# REF-Controller.net
KiCad netlist of a schematic drawn in Altium Designer
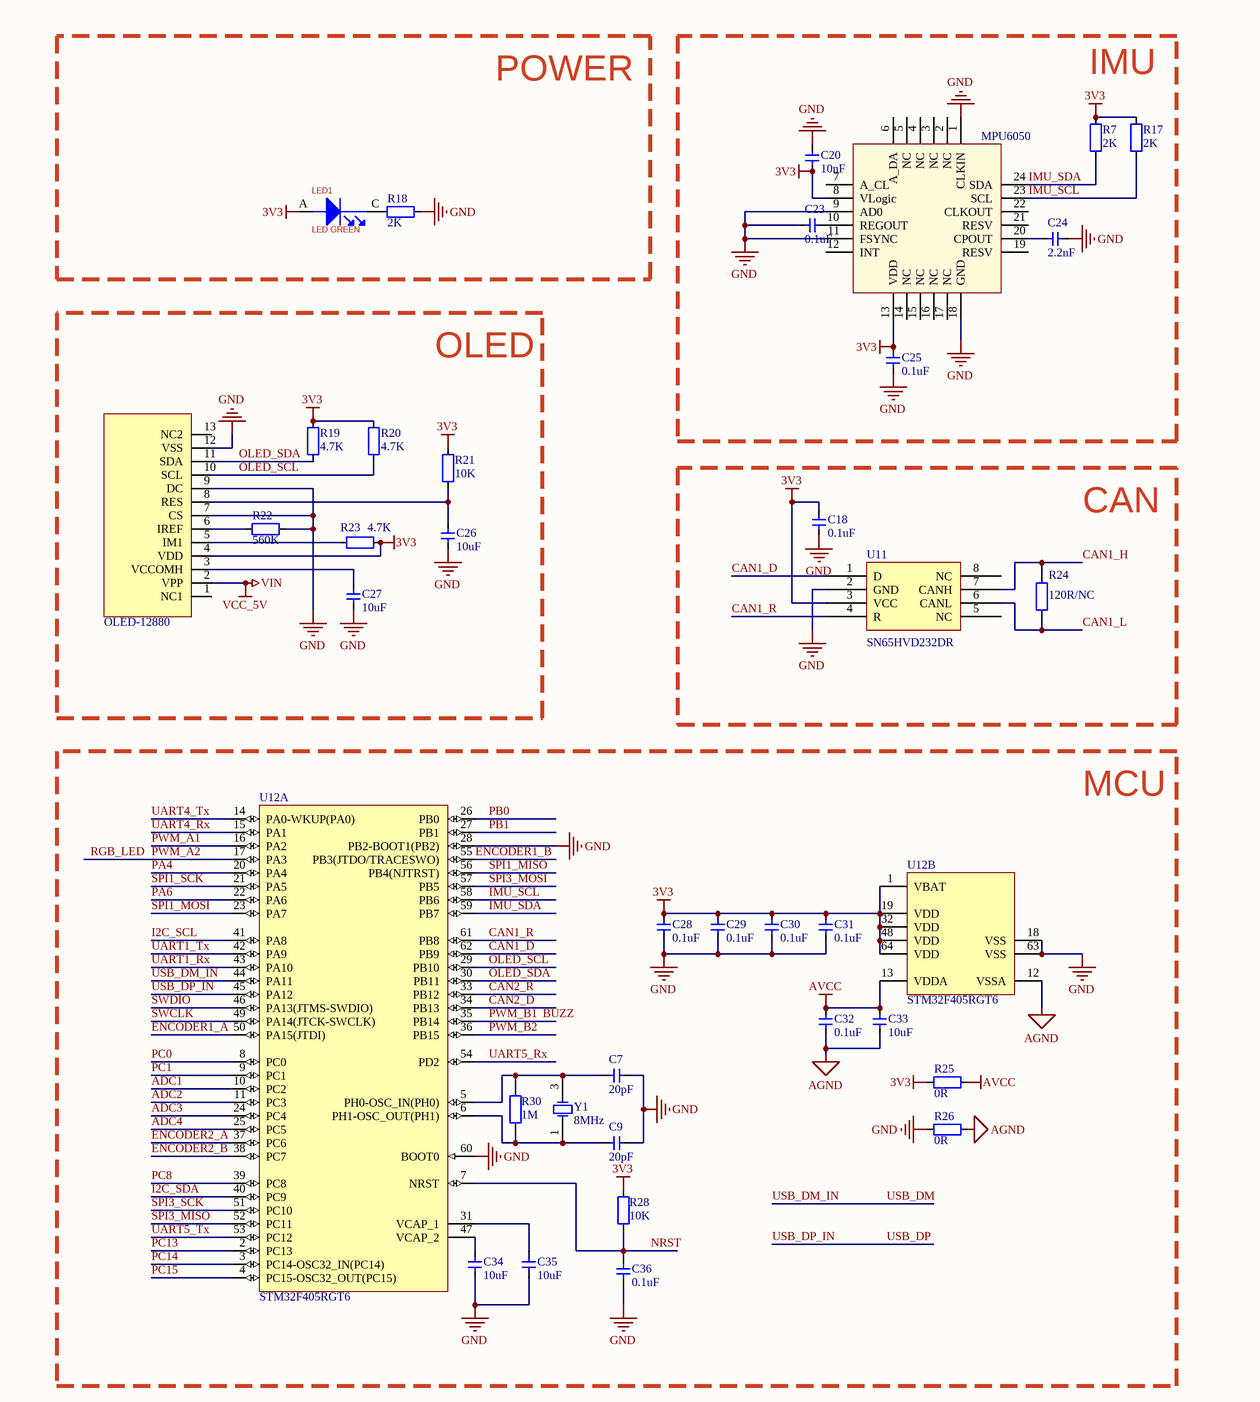
[diagram p0: REF-Controller.SchDoc, top]
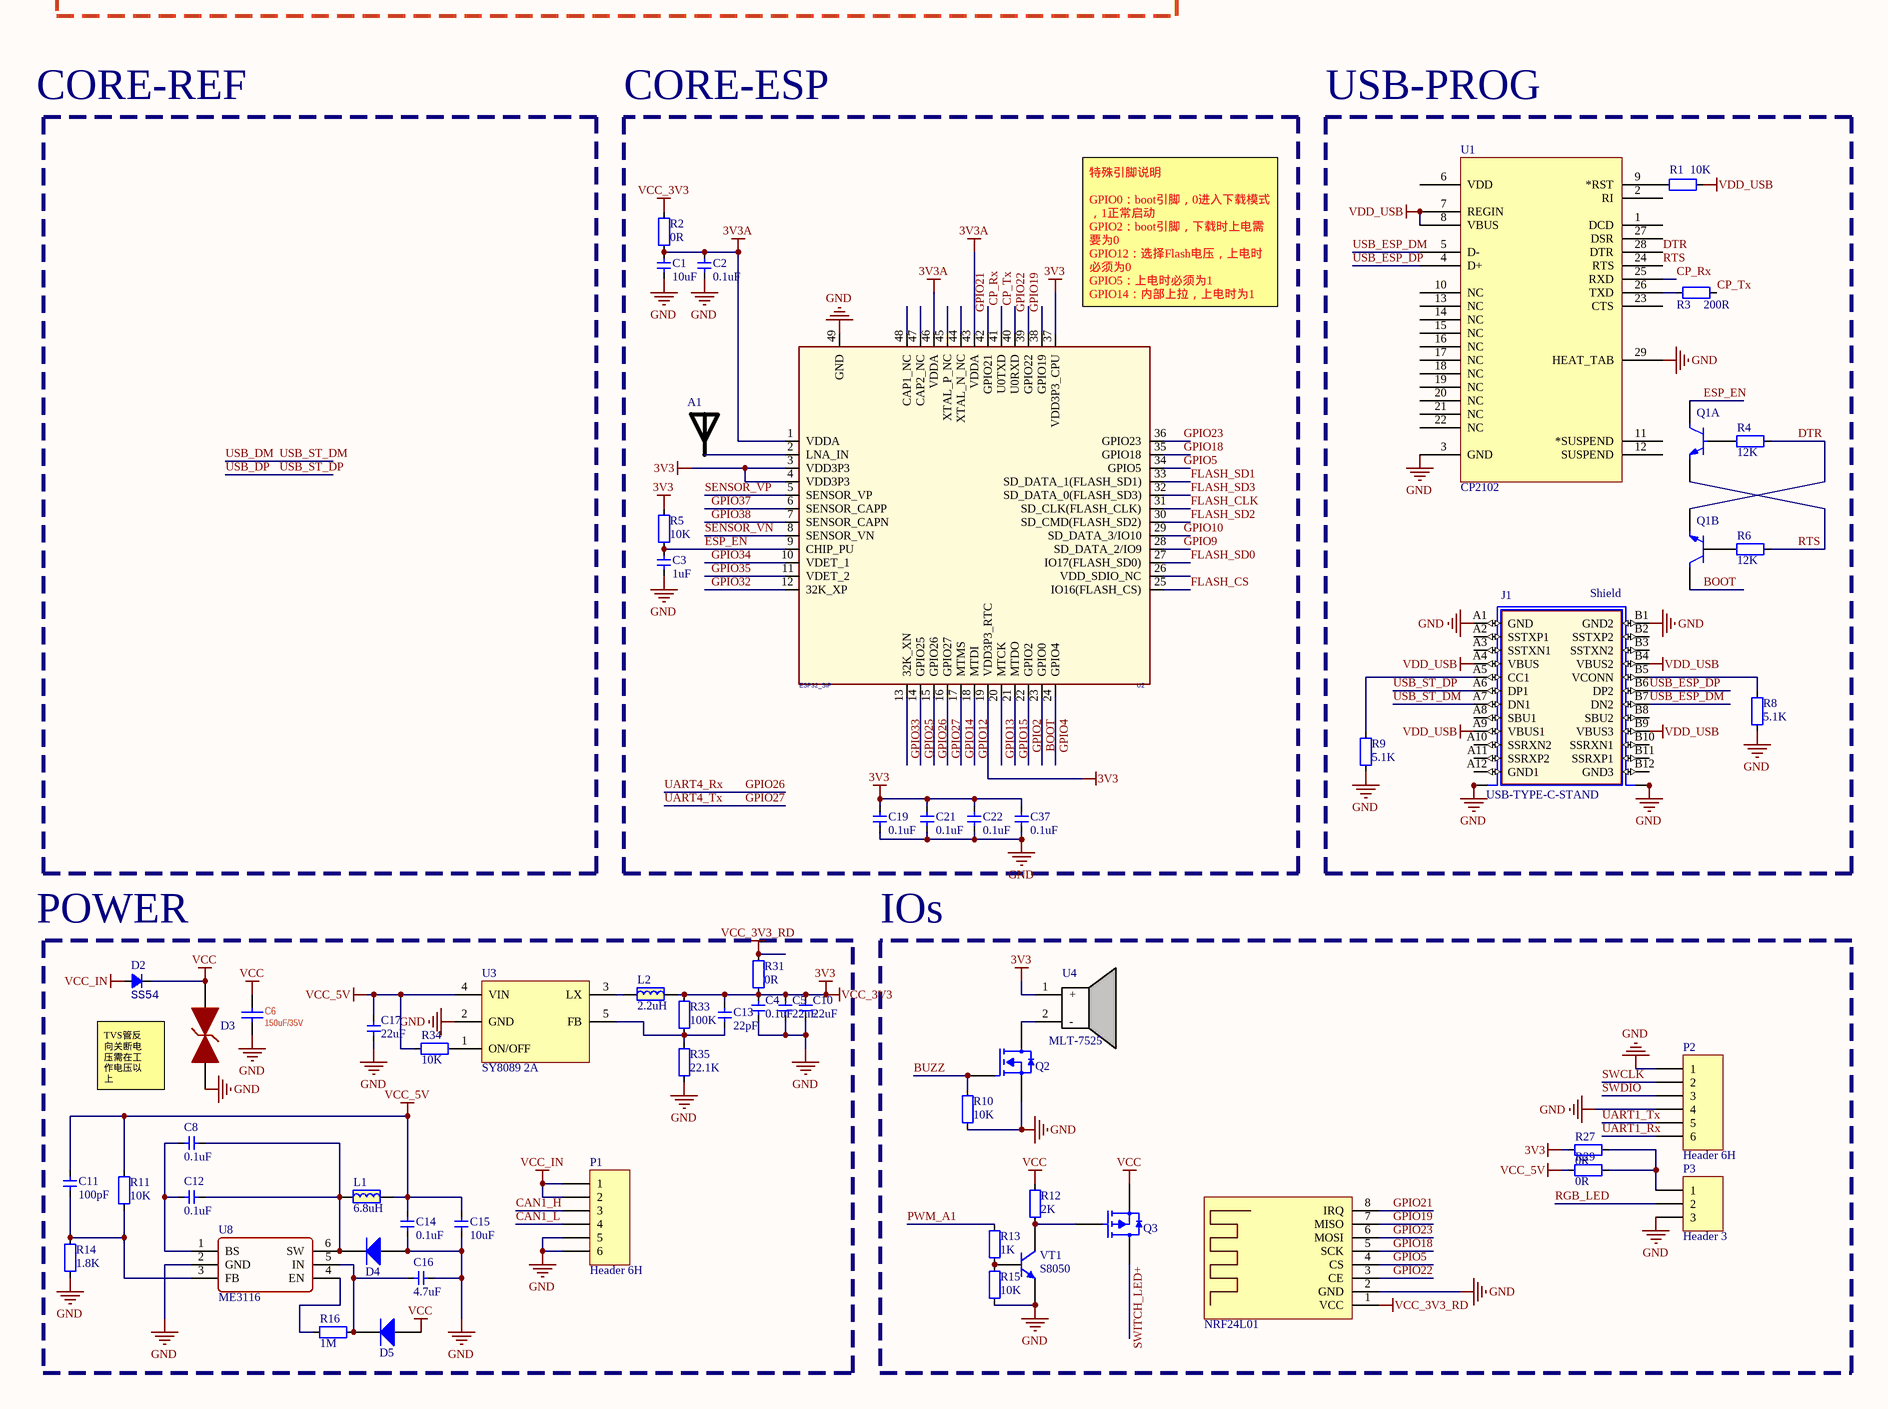
[diagram p1: REF-Controller.SchDoc, bottom]

(export (version "E")
  (design (tool "Eeschema 10.0.6"))
  (components
    (comp (ref "1")
      (value "OLED-12880")
      (footprint "OLED-12880")
      (libsource (lib "mLib") (part "OLED-12880"))
    )
    (comp (ref "A1")
      (value "RAINSUN")
      (footprint "ANT-Rainsun-AN5120")
      (libsource (lib "MyPcbLib") (part "ANT-Rainsun-AP5120"))
    )
    (comp (ref "C1")
      (value "10uF")
      (footprint "CAP_0402")
      (description "Capacitor")
      (libsource (lib "MyPcbLib") (part "电容-0402"))
    )
    (comp (ref "C2")
      (value "0.1uF")
      (footprint "CAP_0402")
      (description "Capacitor")
      (libsource (lib "MyPcbLib") (part "电容-0402"))
    )
    (comp (ref "C3")
      (value "1uF")
      (footprint "CAP_0402")
      (description "Capacitor")
      (libsource (lib "MyPcbLib") (part "电容-0402"))
    )
    (comp (ref "C4")
      (value "0.1uF")
      (footprint "CAP_0402")
      (description "Capacitor")
      (libsource (lib "MyPcbLib") (part "电容-0402"))
    )
    (comp (ref "C5")
      (value "22uF")
      (footprint "C0603")
      (description "Capacitor")
      (libsource (lib "MyPcbLib") (part "电容-0402"))
    )
    (comp (ref "C6")
      (value "150uF/35V")
      (footprint "CAP-SMD_BD8.0-L8.3-W8.3-LS9.3-FD")
      (description "Capacitor, chip, ceramic")
      (fields (field (name "Comment") "220uF/25V"))
      (libsource (lib "OAKUSBFXS") (part "CAP"))
    )
    (comp (ref "C7")
      (value "20pF")
      (footprint "CAP_0402")
      (description "Capacitor")
      (libsource (lib "MyPcbLib") (part "电容-0402"))
    )
    (comp (ref "C8")
      (value "0.1uF")
      (footprint "CAP_0402")
      (description "Capacitor")
      (libsource (lib "MyPcbLib") (part "电容-0402"))
    )
    (comp (ref "C9")
      (value "20pF")
      (footprint "CAP_0402")
      (description "Capacitor")
      (libsource (lib "MyPcbLib") (part "电容-0402"))
    )
    (comp (ref "C10")
      (value "22uF")
      (footprint "C0603")
      (description "Capacitor")
      (libsource (lib "MyPcbLib") (part "电容-0402"))
    )
    (comp (ref "C11")
      (value "100pF")
      (footprint "CAP_0402")
      (description "Capacitor")
      (libsource (lib "MyPcbLib") (part "电容-0402"))
    )
    (comp (ref "C12")
      (value "0.1uF")
      (footprint "CAP_0402")
      (description "Capacitor")
      (libsource (lib "MyPcbLib") (part "电容-0402"))
    )
    (comp (ref "C13")
      (value "22pF")
      (footprint "CAP_0402")
      (description "Capacitor")
      (libsource (lib "MyPcbLib") (part "电容-0402"))
    )
    (comp (ref "C14")
      (value "0.1uF")
      (footprint "CAP_0402")
      (description "Capacitor")
      (libsource (lib "MyPcbLib") (part "电容-0402"))
    )
    (comp (ref "C15")
      (value "10uF")
      (footprint "CAP_0402")
      (description "Capacitor")
      (libsource (lib "MyPcbLib") (part "电容-0402"))
    )
    (comp (ref "C16")
      (value "4.7uF")
      (footprint "C0603")
      (description "Capacitor")
      (libsource (lib "MyPcbLib") (part "电容-0402"))
    )
    (comp (ref "C17")
      (value "22uF")
      (footprint "C0603")
      (description "Capacitor")
      (libsource (lib "MyPcbLib") (part "电容-0402"))
    )
    (comp (ref "C18")
      (value "0.1uF")
      (footprint "CAP_0402")
      (description "Capacitor")
      (libsource (lib "MyPcbLib") (part "电容-0402"))
    )
    (comp (ref "C19")
      (value "0.1uF")
      (footprint "CAP_0402")
      (description "Capacitor")
      (libsource (lib "MyPcbLib") (part "电容-0402"))
    )
    (comp (ref "C20")
      (value "10nF")
      (footprint "CAP_0402")
      (description "Capacitor")
      (libsource (lib "MyPcbLib") (part "电容-0402"))
    )
    (comp (ref "C21")
      (value "0.1uF")
      (footprint "CAP_0402")
      (description "Capacitor")
      (libsource (lib "MyPcbLib") (part "电容-0402"))
    )
    (comp (ref "C22")
      (value "0.1uF")
      (footprint "CAP_0402")
      (description "Capacitor")
      (libsource (lib "MyPcbLib") (part "电容-0402"))
    )
    (comp (ref "C23")
      (value "0.1uF")
      (footprint "CAP_0402")
      (description "Capacitor")
      (libsource (lib "MyPcbLib") (part "电容-0402"))
    )
    (comp (ref "C24")
      (value "2.2nF")
      (footprint "CAP_0402")
      (description "Capacitor")
      (libsource (lib "MyPcbLib") (part "电容-0402"))
    )
    (comp (ref "C25")
      (value "0.1uF")
      (footprint "CAP_0402")
      (description "Capacitor")
      (libsource (lib "MyPcbLib") (part "电容-0402"))
    )
    (comp (ref "C26")
      (value "10uF")
      (footprint "CAP_0402")
      (description "Capacitor")
      (libsource (lib "MyPcbLib") (part "电容-0402"))
    )
    (comp (ref "C27")
      (value "10uF")
      (footprint "CAP_0402")
      (description "Capacitor")
      (libsource (lib "MyPcbLib") (part "电容-0402"))
    )
    (comp (ref "C28")
      (value "0.1uF")
      (footprint "CAP_0402")
      (description "Capacitor")
      (libsource (lib "MyPcbLib") (part "电容-0402"))
    )
    (comp (ref "C29")
      (value "0.1uF")
      (footprint "CAP_0402")
      (description "Capacitor")
      (libsource (lib "MyPcbLib") (part "电容-0402"))
    )
    (comp (ref "C30")
      (value "0.1uF")
      (footprint "CAP_0402")
      (description "Capacitor")
      (libsource (lib "MyPcbLib") (part "电容-0402"))
    )
    (comp (ref "C31")
      (value "0.1uF")
      (footprint "CAP_0402")
      (description "Capacitor")
      (libsource (lib "MyPcbLib") (part "电容-0402"))
    )
    (comp (ref "C32")
      (value "0.1uF")
      (footprint "CAP_0402")
      (description "Capacitor")
      (libsource (lib "MyPcbLib") (part "电容-0402"))
    )
    (comp (ref "C33")
      (value "10uF")
      (footprint "CAP_0402")
      (description "Capacitor")
      (libsource (lib "MyPcbLib") (part "电容-0402"))
    )
    (comp (ref "C34")
      (value "10uF")
      (footprint "CAP_0402")
      (description "Capacitor")
      (libsource (lib "MyPcbLib") (part "电容-0402"))
    )
    (comp (ref "C35")
      (value "10uF")
      (footprint "CAP_0402")
      (description "Capacitor")
      (libsource (lib "MyPcbLib") (part "电容-0402"))
    )
    (comp (ref "C36")
      (value "0.1uF")
      (footprint "CAP_0402")
      (description "Capacitor")
      (libsource (lib "MyPcbLib") (part "电容-0402"))
    )
    (comp (ref "C37")
      (value "0.1uF")
      (footprint "CAP_0402")
      (description "Capacitor")
      (libsource (lib "MyPcbLib") (part "电容-0402"))
    )
    (comp (ref "D2")
      (value "SS54")
      (footprint "DO-214AC")
      (description "Diode")
      (libsource (lib "KitSprout") (part "Diode_SMA"))
    )
    (comp (ref "D3")
      (value "SMBJ28CA")
      (footprint "SMBJ-CA_MFG")
      (libsource (lib "MyPcbLib") (part "SMBJ28CA"))
    )
    (comp (ref "D4")
      (value "二极管-5819W")
      (footprint "SOD-323")
      (description "40V")
      (libsource (lib "MyPcbLib") (part "二极管-5819W"))
    )
    (comp (ref "D5")
      (value "二极管-5819W")
      (footprint "SOD-323")
      (description "40V")
      (libsource (lib "MyPcbLib") (part "二极管-5819W"))
    )
    (comp (ref "J1")
      (value "USB-TYPE-C-STAND")
      (footprint "USB-TYPE-C-STAND")
      (fields (field (name "MP") "632722110112") (field (name "MF") "Wurth Electronics"))
      (libsource (lib "MyPcbLib") (part "USB-TYPE-C-STAND"))
    )
    (comp (ref "L1") (value "6.8uH") (footprint "IND-201612") (libsource (lib "MyPcbLib") (part "电感-201612")))
    (comp (ref "L2")
      (value "2.2uH")
      (footprint "IND-252012A-2R2")
      (libsource (lib "MyPcbLib") (part "电感-201612"))
    )
    (comp (ref "LED1")
      (value "LED GREEN")
      (description "LED GRN SGL RA 25mA 4.1V SMD")
      (libsource (lib "*") (part "LED"))
    )
    (comp (ref "P1")
      (value "Header 6H")
      (footprint "CONN-TH_HC-ZH1.5-6A")
      (description "Header, 6-Pin, Right Angle")
      (fields (field (name "PUBLISHER") "Altium Limited"))
      (libsource (lib "Miscellaneous Connectors") (part "Header 6H"))
    )
    (comp (ref "P2")
      (value "Header 6H")
      (footprint "CONN-TH_HC-ZH1.5-6A-s")
      (description "Header, 6-Pin, Right Angle")
      (fields (field (name "PUBLISHER") "Altium Limited"))
      (libsource (lib "Miscellaneous Connectors") (part "Header 6H"))
    )
    (comp (ref "P3")
      (value "Header 3")
      (footprint "CONN-TH_HC-ZH1.5-3A-S")
      (description "Header, 3-Pin")
      (fields (field (name "PUBLISHER") "Altium Limited"))
      (libsource (lib "Miscellaneous Connectors") (part "Header 3"))
    )
    (comp (ref "Q1")
      (value "BC847BVC-7")
      (footprint "SOT563-6")
      (libsource (lib "MyPcbLib") (part "BC847BVC-7"))
    )
    (comp (ref "Q2")
      (value "AO3400A")
      (footprint "SOT23-3")
      (description "N-MOS")
      (libsource (lib "MyPcbLib") (part "AO3400A"))
    )
    (comp (ref "Q3")
      (value "AO3401A")
      (footprint "SOT23-3")
      (description "P-MOS")
      (libsource (lib "MyPcbLib") (part "AO3401A"))
    )
    (comp (ref "R1")
      (value "10K")
      (footprint "RES_0402_1")
      (description "Resistor")
      (libsource (lib "") (part "电阻-0402_1"))
    )
    (comp (ref "R2")
      (value "0R")
      (footprint "RES_0402_1")
      (description "Resistor")
      (libsource (lib "MyPcbLib") (part "电阻-0402"))
    )
    (comp (ref "R3")
      (value "200R")
      (footprint "RES_0402_1")
      (description "Resistor")
      (libsource (lib "") (part "电阻-0402_1"))
    )
    (comp (ref "R4")
      (value "12K")
      (footprint "RES_0402_1")
      (description "Resistor")
      (libsource (lib "") (part "电阻-0402_1"))
    )
    (comp (ref "R5")
      (value "10K")
      (footprint "RES_0402_1")
      (description "Resistor")
      (libsource (lib "MyPcbLib") (part "电阻-0402"))
    )
    (comp (ref "R6")
      (value "12K")
      (footprint "RES_0402_1")
      (description "Resistor")
      (libsource (lib "") (part "电阻-0402_1"))
    )
    (comp (ref "R7")
      (value "2K")
      (footprint "RES_0402_1")
      (description "Resistor")
      (libsource (lib "") (part "电阻-0402_2"))
    )
    (comp (ref "R8")
      (value "5.1K")
      (footprint "RES_0402_1")
      (description "Resistor")
      (libsource (lib "MyPcbLib") (part "电阻-0402"))
    )
    (comp (ref "R9")
      (value "5.1K")
      (footprint "RES_0402_1")
      (description "Resistor")
      (libsource (lib "MyPcbLib") (part "电阻-0402"))
    )
    (comp (ref "R10")
      (value "10K")
      (footprint "RES_0402_1")
      (description "Resistor")
      (libsource (lib "") (part "电阻-0402_2"))
    )
    (comp (ref "R11")
      (value "10K")
      (footprint "RES_0402_1")
      (description "Resistor")
      (libsource (lib "") (part "电阻-0402_2"))
    )
    (comp (ref "R12")
      (value "2K")
      (footprint "RES_0402_1")
      (description "Resistor")
      (libsource (lib "") (part "电阻-0402_2"))
    )
    (comp (ref "R13")
      (value "1K")
      (footprint "RES_0402_1")
      (description "Resistor")
      (libsource (lib "MyPcbLib") (part "电阻-0402"))
    )
    (comp (ref "R14")
      (value "1.8K")
      (footprint "RES_0402_1")
      (description "Resistor")
      (libsource (lib "") (part "电阻-0402_2"))
    )
    (comp (ref "R15")
      (value "10K")
      (footprint "RES_0402_1")
      (description "Resistor")
      (libsource (lib "MyPcbLib") (part "电阻-0402"))
    )
    (comp (ref "R16")
      (value "1M")
      (footprint "RES_0402_1")
      (description "Resistor")
      (libsource (lib "") (part "电阻-0402_1"))
    )
    (comp (ref "R17")
      (value "2K")
      (footprint "RES_0402_1")
      (description "Resistor")
      (libsource (lib "") (part "电阻-0402_2"))
    )
    (comp (ref "R18")
      (value "2K")
      (footprint "RES_0402_1")
      (description "Resistor")
      (libsource (lib "") (part "电阻-0402_1"))
    )
    (comp (ref "R19")
      (value "4.7K")
      (footprint "RES_0402_1")
      (description "Resistor")
      (libsource (lib "") (part "电阻-0402_2"))
    )
    (comp (ref "R20")
      (value "4.7K")
      (footprint "RES_0402_1")
      (description "Resistor")
      (libsource (lib "") (part "电阻-0402_2"))
    )
    (comp (ref "R21")
      (value "10K")
      (footprint "RES_0402_1")
      (description "Resistor")
      (libsource (lib "") (part "电阻-0402_2"))
    )
    (comp (ref "R22")
      (value "560K")
      (footprint "RES_0402_1")
      (description "Resistor")
      (libsource (lib "") (part "电阻-0402_3"))
    )
    (comp (ref "R23")
      (value "4.7K")
      (footprint "RES_0402_1")
      (description "Resistor")
      (libsource (lib "") (part "电阻-0402_3"))
    )
    (comp (ref "R24")
      (value "120R/NC")
      (footprint "RES_0402_1")
      (description "Resistor")
      (libsource (lib "MyPcbLib") (part "电阻-0402"))
    )
    (comp (ref "R25")
      (value "0R")
      (footprint "RES_0402_1")
      (description "Resistor")
      (libsource (lib "") (part "电阻-0402_1"))
    )
    (comp (ref "R26")
      (value "0R")
      (footprint "RES_0402_1")
      (description "Resistor")
      (libsource (lib "") (part "电阻-0402_1"))
    )
    (comp (ref "R27")
      (value "0R")
      (footprint "RES_0402_1")
      (description "Resistor")
      (libsource (lib "") (part "电阻-0402_1"))
    )
    (comp (ref "R28")
      (value "10K")
      (footprint "RES_0402_1")
      (description "Resistor")
      (libsource (lib "") (part "电阻-0402_2"))
    )
    (comp (ref "R29")
      (value "0R")
      (footprint "RES_0402_1")
      (description "Resistor")
      (libsource (lib "") (part "电阻-0402_1"))
    )
    (comp (ref "R30")
      (value "1M")
      (footprint "RES_0402")
      (description "Resistor")
      (libsource (lib "MyPcbLib") (part "电阻-0402"))
    )
    (comp (ref "R31")
      (value "0R")
      (footprint "RES_0402_1")
      (description "Resistor")
      (libsource (lib "") (part "电阻-0402_2"))
    )
    (comp (ref "R33")
      (value "100K")
      (footprint "RES_0402_1")
      (description "Resistor")
      (libsource (lib "") (part "电阻-0402_2"))
    )
    (comp (ref "R34")
      (value "10K")
      (footprint "RES_0402_1")
      (description "Resistor")
      (libsource (lib "") (part "电阻-0402_1"))
    )
    (comp (ref "R35")
      (value "22.1K")
      (footprint "RES_0402_1")
      (description "Resistor")
      (libsource (lib "") (part "电阻-0402_2"))
    )
    (comp (ref "U1")
      (value "CP2102")
      (footprint "QFN-28")
      (description "USB转TTL")
      (libsource (lib "mLib") (part "CP2102"))
    )
    (comp (ref "U2")
      (value "ESP32_SIP")
      (footprint "QFN-48_7X7")
      (libsource (lib "mLib") (part "ESP32-PICO"))
    )
    (comp (ref "U3")
      (value "SY8089 2A")
      (footprint "SOT23-5")
      (description "LDO")
      (libsource (lib "Schlib1") (part "SY8089"))
    )
    (comp (ref "U4")
      (value "MLT-7525")
      (footprint "BUZ-SMD_4P-L7.5-W7.5-P7.59-TL")
      (libsource (lib "MyPcbLib") (part "DET402"))
    )
    (comp (ref "U7")
      (value "NRF24L01")
      (footprint "NRF24L01-MODULE")
      (libsource (lib "MyPcbLib") (part "NRF24L01模块"))
    )
    (comp (ref "U8")
      (value "ME3116")
      (footprint "SOT23-6")
      (description "DC-DC")
      (libsource (lib "MyPcbLib") (part "ME3116"))
    )
    (comp (ref "U10")
      (value "MPU6050")
      (footprint "QFN-24")
      (description "六轴传感器")
      (libsource (lib "mLib") (part "MPU6050"))
    )
    (comp (ref "U11")
      (value "SN65HVD232D")
      (footprint "SO-8")
      (fields
        (field (name "MANUFACTURER") "Texas Instruments")
        (field (name "MANUFACTURER PART NUMBER") "SN65HVD232DR")
      )
      (libsource (lib "MyPcbLib") (part "SN65HVD232D"))
    )
    (comp (ref "U12")
      (value "STM32F405RGT6")
      (footprint "LQFP-64_N")
      (fields (field (name "MANUFACTURER") "STMicroelectronics"))
      (libsource (lib "STMicroelectronics STM32 F4") (part "STM32F405RGT6"))
    )
    (comp (ref "VT1")
      (value "S8050")
      (footprint "SMT_TRIODE_NPN")
      (description "Surface mount NPN transistor, package SOT-23")
      (libsource (lib "MyPcbLib") (part "SMT_TRIODE_NPN"))
    )
    (comp (ref "Y1")
      (value "8MHz")
      (footprint "LC-SMD-3225_4P")
      (description "Crystal")
      (fields (field (name "Comment") "XTAL-4"))
      (libsource (lib "rpi") (part "XTAL-4"))
    )
  )
  (nets
    (net (code "1") (name "/ADC1") (class "Default")
      (node (ref "U12") (pin "10") (pinfunction "PC2_10") (pintype "bidirectional"))
    )
    (net (code "2") (name "/ADC2") (class "Default")
      (node (ref "U12") (pin "11") (pinfunction "PC3_11") (pintype "bidirectional"))
    )
    (net (code "3") (name "/ADC3") (class "Default")
      (node (ref "U12") (pin "24") (pinfunction "PC4_24") (pintype "bidirectional"))
    )
    (net (code "4") (name "/ADC4") (class "Default")
      (node (ref "U12") (pin "25") (pinfunction "PC5_25") (pintype "bidirectional"))
    )
    (net (code "5") (name "/BOOT") (class "Default")
      (node (ref "Q1") (pin "3") (pinfunction "C2_3") (pintype "passive"))
      (node (ref "U2") (pin "23") (pinfunction "GPIO0_23") (pintype "passive"))
    )
    (net (code "6") (name "/BUZZ") (class "Default")
      (node (ref "Q2") (pin "1") (pinfunction "G_1") (pintype "passive"))
      (node (ref "R10") (pin "2") (pinfunction "2_2") (pintype "passive"))
      (node (ref "U12") (pin "35") (pinfunction "PB14_35") (pintype "bidirectional"))
    )
    (net (code "7") (name "/CAN1_D") (class "Default")
      (node (ref "U11") (pin "1") (pinfunction "D_1") (pintype "passive"))
      (node (ref "U12") (pin "62") (pinfunction "PB9_62") (pintype "bidirectional"))
    )
    (net (code "8") (name "/CAN1_H") (class "Default")
      (node (ref "P1") (pin "3") (pinfunction "3_3") (pintype "passive"))
      (node (ref "R24") (pin "1") (pinfunction "1_1") (pintype "passive"))
      (node (ref "U11") (pin "7") (pinfunction "CANH_7") (pintype "passive"))
    )
    (net (code "9") (name "/CAN1_L") (class "Default")
      (node (ref "P1") (pin "4") (pinfunction "4_4") (pintype "passive"))
      (node (ref "R24") (pin "2") (pinfunction "2_2") (pintype "passive"))
      (node (ref "U11") (pin "6") (pinfunction "CANL_6") (pintype "passive"))
    )
    (net (code "10") (name "/CAN1_R") (class "Default")
      (node (ref "U11") (pin "4") (pinfunction "R_4") (pintype "passive"))
      (node (ref "U12") (pin "61") (pinfunction "PB8_61") (pintype "bidirectional"))
    )
    (net (code "11") (name "/CAN2_D") (class "Default")
      (node (ref "U12") (pin "34") (pinfunction "PB13_34") (pintype "bidirectional"))
    )
    (net (code "12") (name "/CAN2_R") (class "Default")
      (node (ref "U12") (pin "33") (pinfunction "PB12_33") (pintype "bidirectional"))
    )
    (net (code "13") (name "/CP_Rx") (class "Default")
      (node (ref "U1") (pin "25") (pinfunction "RXD_25") (pintype "passive"))
      (node (ref "U2") (pin "41") (pinfunction "U0TXD_41") (pintype "power_in"))
    )
    (net (code "14") (name "/CP_Tx") (class "Default")
      (node (ref "R3") (pin "1") (pinfunction "1_1") (pintype "passive"))
      (node (ref "U2") (pin "40") (pinfunction "U0RXD_40") (pintype "power_in"))
    )
    (net (code "15") (name "/DTR") (class "Default")
      (node (ref "Q1") (pin "4") (pinfunction "E2_4") (pintype "passive"))
      (node (ref "R4") (pin "1") (pinfunction "1_1") (pintype "passive"))
      (node (ref "U1") (pin "28") (pinfunction "DTR_28") (pintype "passive"))
    )
    (net (code "16") (name "/ENCODER1_A") (class "Default")
      (node (ref "U12") (pin "50") (pinfunction "PA15(JTDI)_50") (pintype "bidirectional"))
    )
    (net (code "17") (name "/ENCODER1_B") (class "Default")
      (node (ref "U12") (pin "55") (pinfunction "PB3(JTDO/TRACESWO)_55") (pintype "bidirectional"))
    )
    (net (code "18") (name "/ENCODER2_A") (class "Default")
      (node (ref "U12") (pin "37") (pinfunction "PC6_37") (pintype "bidirectional"))
    )
    (net (code "19") (name "/ENCODER2_B") (class "Default")
      (node (ref "U12") (pin "38") (pinfunction "PC7_38") (pintype "bidirectional"))
    )
    (net (code "20") (name "/ESP_EN") (class "Default")
      (node (ref "C3") (pin "1") (pinfunction "1_1") (pintype "passive"))
      (node (ref "Q1") (pin "6") (pinfunction "C1_6") (pintype "passive"))
      (node (ref "R5") (pin "2") (pinfunction "2_2") (pintype "passive"))
      (node (ref "U2") (pin "9") (pinfunction "CHIP_PU_9") (pintype "passive"))
    )
    (net (code "21") (name "/FLASH_CLK") (class "Default")
      (node (ref "U2") (pin "31") (pinfunction "SD_CLK(FLASH_CLK)_31") (pintype "passive"))
    )
    (net (code "22") (name "/FLASH_CS") (class "Default")
      (node (ref "U2") (pin "25") (pinfunction "IO16(FLASH_CS)_25") (pintype "passive"))
    )
    (net (code "23") (name "/FLASH_SD0") (class "Default")
      (node (ref "U2") (pin "27") (pinfunction "IO17(FLASH_SD0)_27") (pintype "passive"))
    )
    (net (code "24") (name "/FLASH_SD1") (class "Default")
      (node (ref "U2") (pin "33") (pinfunction "SD_DATA_1(FLASH_SD1)_33") (pintype "passive"))
    )
    (net (code "25") (name "/FLASH_SD2") (class "Default")
      (node (ref "U2") (pin "30") (pinfunction "SD_CMD(FLASH_SD2)_30") (pintype "passive"))
    )
    (net (code "26") (name "/FLASH_SD3") (class "Default")
      (node (ref "U2") (pin "32") (pinfunction "SD_DATA_0(FLASH_SD3)_32") (pintype "passive"))
    )
    (net (code "27") (name "/GPIO2") (class "Default")
      (node (ref "U2") (pin "22") (pinfunction "GPIO2_22") (pintype "passive"))
    )
    (net (code "28") (name "/GPIO4") (class "Default")
      (node (ref "U2") (pin "24") (pinfunction "GPIO4_24") (pintype "passive"))
    )
    (net (code "29") (name "/GPIO5") (class "Default")
      (node (ref "U2") (pin "34") (pinfunction "GPIO5_34") (pintype "passive"))
      (node (ref "U7") (pin "4") (pinfunction "CS_4") (pintype "passive"))
    )
    (net (code "30") (name "/GPIO9") (class "Default")
      (node (ref "U2") (pin "28") (pinfunction "SD_DATA_2/IO9_28") (pintype "passive"))
    )
    (net (code "31") (name "/GPIO10") (class "Default")
      (node (ref "U2") (pin "29") (pinfunction "SD_DATA_3/IO10_29") (pintype "passive"))
    )
    (net (code "32") (name "/GPIO12") (class "Default")
      (node (ref "U2") (pin "18") (pinfunction "MTDI_18") (pintype "passive"))
    )
    (net (code "33") (name "/GPIO13") (class "Default")
      (node (ref "U2") (pin "20") (pinfunction "MTCK_20") (pintype "passive"))
    )
    (net (code "34") (name "/GPIO14") (class "Default")
      (node (ref "U2") (pin "17") (pinfunction "MTMS_17") (pintype "passive"))
    )
    (net (code "35") (name "/GPIO15") (class "Default")
      (node (ref "U2") (pin "21") (pinfunction "MTDO_21") (pintype "passive"))
    )
    (net (code "36") (name "/GPIO18") (class "Default")
      (node (ref "U2") (pin "35") (pinfunction "GPIO18_35") (pintype "passive"))
      (node (ref "U7") (pin "5") (pinfunction "SCK_5") (pintype "passive"))
    )
    (net (code "37") (name "/GPIO19") (class "Default")
      (node (ref "U2") (pin "38") (pinfunction "GPIO19_38") (pintype "passive"))
      (node (ref "U7") (pin "7") (pinfunction "MISO_7") (pintype "passive"))
    )
    (net (code "38") (name "/GPIO21") (class "Default")
      (node (ref "U2") (pin "42") (pinfunction "GPIO21_42") (pintype "passive"))
      (node (ref "U7") (pin "8") (pinfunction "IRQ_8") (pintype "passive"))
    )
    (net (code "39") (name "/GPIO22") (class "Default")
      (node (ref "U2") (pin "39") (pinfunction "GPIO22_39") (pintype "passive"))
      (node (ref "U7") (pin "3") (pinfunction "CE_3") (pintype "passive"))
    )
    (net (code "40") (name "/GPIO23") (class "Default")
      (node (ref "U2") (pin "36") (pinfunction "GPIO23_36") (pintype "passive"))
      (node (ref "U7") (pin "6") (pinfunction "MOSI_6") (pintype "passive"))
    )
    (net (code "41") (name "/GPIO25") (class "Default")
      (node (ref "U2") (pin "14") (pinfunction "GPIO25_14") (pintype "passive"))
    )
    (net (code "42") (name "/GPIO26") (class "Default")
      (node (ref "U12") (pin "15") (pinfunction "PA1_15") (pintype "bidirectional"))
      (node (ref "U2") (pin "15") (pinfunction "GPIO26_15") (pintype "passive"))
    )
    (net (code "43") (name "/GPIO27") (class "Default")
      (node (ref "U12") (pin "14") (pinfunction "PA0-WKUP(PA0)_14") (pintype "bidirectional"))
      (node (ref "U2") (pin "16") (pinfunction "GPIO27_16") (pintype "passive"))
    )
    (net (code "44") (name "/GPIO32") (class "Default")
      (node (ref "U2") (pin "12") (pinfunction "32K_XP_12") (pintype "passive"))
    )
    (net (code "45") (name "/GPIO33") (class "Default")
      (node (ref "U2") (pin "13") (pinfunction "32K_XN_13") (pintype "passive"))
    )
    (net (code "46") (name "/GPIO34") (class "Default")
      (node (ref "U2") (pin "10") (pinfunction "VDET_1_10") (pintype "passive"))
    )
    (net (code "47") (name "/GPIO35") (class "Default")
      (node (ref "U2") (pin "11") (pinfunction "VDET_2_11") (pintype "passive"))
    )
    (net (code "48") (name "/GPIO37") (class "Default")
      (node (ref "U2") (pin "6") (pinfunction "SENSOR_CAPP_6") (pintype "passive"))
    )
    (net (code "49") (name "/GPIO38") (class "Default")
      (node (ref "U2") (pin "7") (pinfunction "SENSOR_CAPN_7") (pintype "passive"))
    )
    (net (code "50") (name "/I2C_SCL") (class "Default")
      (node (ref "U12") (pin "41") (pinfunction "PA8_41") (pintype "bidirectional"))
    )
    (net (code "51") (name "/I2C_SDA") (class "Default")
      (node (ref "U12") (pin "40") (pinfunction "PC9_40") (pintype "bidirectional"))
    )
    (net (code "52") (name "/IMU_SCL") (class "Default")
      (node (ref "R17") (pin "1") (pinfunction "1_1") (pintype "passive"))
      (node (ref "U10") (pin "23") (pinfunction "SCL_23") (pintype "passive"))
      (node (ref "U12") (pin "58") (pinfunction "PB6_58") (pintype "bidirectional"))
    )
    (net (code "53") (name "/IMU_SDA") (class "Default")
      (node (ref "R7") (pin "1") (pinfunction "1_1") (pintype "passive"))
      (node (ref "U10") (pin "24") (pinfunction "SDA_24") (pintype "passive"))
      (node (ref "U12") (pin "59") (pinfunction "PB7_59") (pintype "bidirectional"))
    )
    (net (code "54") (name "/NRST") (class "Default")
      (node (ref "C36") (pin "2") (pinfunction "2_2") (pintype "passive"))
      (node (ref "R28") (pin "1") (pinfunction "1_1") (pintype "passive"))
      (node (ref "U12") (pin "7") (pinfunction "NRST_7") (pintype "bidirectional"))
    )
    (net (code "55") (name "/OLED_SCL") (class "Default")
      (node (ref "1") (pin "10") (pinfunction "SCL_10") (pintype "passive"))
      (node (ref "R20") (pin "1") (pinfunction "1_1") (pintype "passive"))
      (node (ref "U12") (pin "29") (pinfunction "PB10_29") (pintype "bidirectional"))
    )
    (net (code "56") (name "/OLED_SDA") (class "Default")
      (node (ref "1") (pin "11") (pinfunction "SDA_11") (pintype "passive"))
      (node (ref "R19") (pin "1") (pinfunction "1_1") (pintype "passive"))
      (node (ref "U12") (pin "30") (pinfunction "PB11_30") (pintype "bidirectional"))
    )
    (net (code "57") (name "/PA4") (class "Default")
      (node (ref "U12") (pin "20") (pinfunction "PA4_20") (pintype "bidirectional"))
    )
    (net (code "58") (name "/PA6") (class "Default")
      (node (ref "U12") (pin "22") (pinfunction "PA6_22") (pintype "bidirectional"))
    )
    (net (code "59") (name "/PB0") (class "Default")
      (node (ref "U12") (pin "26") (pinfunction "PB0_26") (pintype "bidirectional"))
    )
    (net (code "60") (name "/PB1") (class "Default")
      (node (ref "U12") (pin "27") (pinfunction "PB1_27") (pintype "bidirectional"))
    )
    (net (code "61") (name "/PC0") (class "Default")
      (node (ref "U12") (pin "8") (pinfunction "PC0_8") (pintype "bidirectional"))
    )
    (net (code "62") (name "/PC1") (class "Default")
      (node (ref "U12") (pin "9") (pinfunction "PC1_9") (pintype "bidirectional"))
    )
    (net (code "63") (name "/PC8") (class "Default")
      (node (ref "U12") (pin "39") (pinfunction "PC8_39") (pintype "bidirectional"))
    )
    (net (code "64") (name "/PC13") (class "Default")
      (node (ref "U12") (pin "2") (pinfunction "PC13_2") (pintype "bidirectional"))
    )
    (net (code "65") (name "/PC14") (class "Default")
      (node (ref "U12") (pin "3") (pinfunction "PC14-OSC32_IN(PC14)_3") (pintype "bidirectional"))
    )
    (net (code "66") (name "/PC15") (class "Default")
      (node (ref "U12") (pin "4") (pinfunction "PC15-OSC32_OUT(PC15)_4") (pintype "bidirectional"))
    )
    (net (code "67") (name "/PWM_A1") (class "Default")
      (node (ref "R13") (pin "1") (pinfunction "1_1") (pintype "passive"))
      (node (ref "U12") (pin "16") (pinfunction "PA2_16") (pintype "bidirectional"))
    )
    (net (code "68") (name "/PWM_A2") (class "Default")
      (node (ref "P3") (pin "2") (pinfunction "2_2") (pintype "passive"))
      (node (ref "U12") (pin "17") (pinfunction "PA3_17") (pintype "bidirectional"))
    )
    (net (code "69") (name "/PWM_B2") (class "Default")
      (node (ref "U12") (pin "36") (pinfunction "PB15_36") (pintype "bidirectional"))
    )
    (net (code "70") (name "/RTS") (class "Default")
      (node (ref "Q1") (pin "1") (pinfunction "E1_1") (pintype "passive"))
      (node (ref "R6") (pin "1") (pinfunction "1_1") (pintype "passive"))
      (node (ref "U1") (pin "24") (pinfunction "RTS_24") (pintype "passive"))
    )
    (net (code "71") (name "/SENSOR_VN") (class "Default")
      (node (ref "U2") (pin "8") (pinfunction "SENSOR_VN_8") (pintype "passive"))
    )
    (net (code "72") (name "/SENSOR_VP") (class "Default")
      (node (ref "U2") (pin "5") (pinfunction "SENSOR_VP_5") (pintype "passive"))
    )
    (net (code "73") (name "/SPI1_MISO") (class "Default")
      (node (ref "U12") (pin "56") (pinfunction "PB4(NJTRST)_56") (pintype "bidirectional"))
    )
    (net (code "74") (name "/SPI1_MOSI") (class "Default")
      (node (ref "U12") (pin "23") (pinfunction "PA7_23") (pintype "bidirectional"))
    )
    (net (code "75") (name "/SPI1_SCK") (class "Default")
      (node (ref "U12") (pin "21") (pinfunction "PA5_21") (pintype "bidirectional"))
    )
    (net (code "76") (name "/SPI3_MISO") (class "Default")
      (node (ref "U12") (pin "52") (pinfunction "PC11_52") (pintype "bidirectional"))
    )
    (net (code "77") (name "/SPI3_MOSI") (class "Default")
      (node (ref "U12") (pin "57") (pinfunction "PB5_57") (pintype "bidirectional"))
    )
    (net (code "78") (name "/SPI3_SCK") (class "Default")
      (node (ref "U12") (pin "51") (pinfunction "PC10_51") (pintype "bidirectional"))
    )
    (net (code "79") (name "/SWCLK") (class "Default")
      (node (ref "P2") (pin "2") (pinfunction "2_2") (pintype "passive"))
      (node (ref "U12") (pin "49") (pinfunction "PA14(JTCK-SWCLK)_49") (pintype "bidirectional"))
    )
    (net (code "80") (name "/SWDIO") (class "Default")
      (node (ref "P2") (pin "3") (pinfunction "3_3") (pintype "passive"))
      (node (ref "U12") (pin "46") (pinfunction "PA13(JTMS-SWDIO)_46") (pintype "bidirectional"))
    )
    (net (code "81") (name "/SWITCH_LED+") (class "Default")
      (node (ref "Q3") (pin "3") (pinfunction "D_3") (pintype "passive"))
    )
    (net (code "82") (name "/UART1_Rx") (class "Default")
      (node (ref "P2") (pin "6") (pinfunction "6_6") (pintype "passive"))
      (node (ref "U12") (pin "43") (pinfunction "PA10_43") (pintype "bidirectional"))
    )
    (net (code "83") (name "/UART1_Tx") (class "Default")
      (node (ref "P2") (pin "5") (pinfunction "5_5") (pintype "passive"))
      (node (ref "U12") (pin "42") (pinfunction "PA9_42") (pintype "bidirectional"))
    )
    (net (code "84") (name "/UART5_Rx") (class "Default")
      (node (ref "U12") (pin "54") (pinfunction "PD2_54") (pintype "bidirectional"))
    )
    (net (code "85") (name "/UART5_Tx") (class "Default")
      (node (ref "U12") (pin "53") (pinfunction "PC12_53") (pintype "bidirectional"))
    )
    (net (code "86") (name "/USB_DM") (class "Default")
      (node (ref "J1") (pin "A7") (pinfunction "DN1_A7") (pintype "bidirectional"))
      (node (ref "U12") (pin "44") (pinfunction "PA11_44") (pintype "bidirectional"))
    )
    (net (code "87") (name "/USB_DP") (class "Default")
      (node (ref "J1") (pin "A6") (pinfunction "DP1_A6") (pintype "bidirectional"))
      (node (ref "U12") (pin "45") (pinfunction "PA12_45") (pintype "bidirectional"))
    )
    (net (code "88") (name "/USB_ESP_DM") (class "Default")
      (node (ref "J1") (pin "B7") (pinfunction "DN2_B7") (pintype "bidirectional"))
      (node (ref "U1") (pin "5") (pinfunction "D-_5") (pintype "passive"))
    )
    (net (code "89") (name "/USB_ESP_DP") (class "Default")
      (node (ref "J1") (pin "B6") (pinfunction "DP2_B6") (pintype "bidirectional"))
      (node (ref "U1") (pin "4") (pinfunction "D+_4") (pintype "passive"))
    )
    (net (code "90") (name "3V3") (class "Default")
      (node (ref "1") (pin "4") (pinfunction "VDD_4") (pintype "passive"))
      (node (ref "C10") (pin "2") (pinfunction "2_2") (pintype "passive"))
      (node (ref "C13") (pin "2") (pinfunction "2_2") (pintype "passive"))
      (node (ref "C18") (pin "2") (pinfunction "2_2") (pintype "passive"))
      (node (ref "C19") (pin "2") (pinfunction "2_2") (pintype "passive"))
      (node (ref "C20") (pin "1") (pinfunction "1_1") (pintype "passive"))
      (node (ref "C21") (pin "2") (pinfunction "2_2") (pintype "passive"))
      (node (ref "C22") (pin "2") (pinfunction "2_2") (pintype "passive"))
      (node (ref "C25") (pin "2") (pinfunction "2_2") (pintype "passive"))
      (node (ref "C28") (pin "2") (pinfunction "2_2") (pintype "passive"))
      (node (ref "C29") (pin "2") (pinfunction "2_2") (pintype "passive"))
      (node (ref "C30") (pin "2") (pinfunction "2_2") (pintype "passive"))
      (node (ref "C31") (pin "2") (pinfunction "2_2") (pintype "passive"))
      (node (ref "C37") (pin "2") (pinfunction "2_2") (pintype "passive"))
      (node (ref "C4") (pin "2") (pinfunction "2_2") (pintype "passive"))
      (node (ref "C5") (pin "2") (pinfunction "2_2") (pintype "passive"))
      (node (ref "L2") (pin "2") (pinfunction "2_2") (pintype "passive"))
      (node (ref "LED1") (pin "A") (pinfunction "ANODE_A") (pintype "passive"))
      (node (ref "R17") (pin "2") (pinfunction "2_2") (pintype "passive"))
      (node (ref "R19") (pin "2") (pinfunction "2_2") (pintype "passive"))
      (node (ref "R2") (pin "1") (pinfunction "1_1") (pintype "passive"))
      (node (ref "R20") (pin "2") (pinfunction "2_2") (pintype "passive"))
      (node (ref "R21") (pin "2") (pinfunction "2_2") (pintype "passive"))
      (node (ref "R23") (pin "2") (pinfunction "2_2") (pintype "passive"))
      (node (ref "R25") (pin "2") (pinfunction "2_2") (pintype "passive"))
      (node (ref "R27") (pin "2") (pinfunction "2_2") (pintype "passive"))
      (node (ref "R28") (pin "2") (pinfunction "2_2") (pintype "passive"))
      (node (ref "R31") (pin "1") (pinfunction "1_1") (pintype "passive"))
      (node (ref "R33") (pin "2") (pinfunction "2_2") (pintype "passive"))
      (node (ref "R5") (pin "1") (pinfunction "1_1") (pintype "passive"))
      (node (ref "R7") (pin "2") (pinfunction "2_2") (pintype "passive"))
      (node (ref "U10") (pin "13") (pinfunction "VDD_13") (pintype "passive"))
      (node (ref "U10") (pin "8") (pinfunction "VLogic_8") (pintype "passive"))
      (node (ref "U11") (pin "3") (pinfunction "VCC_3") (pintype "passive"))
      (node (ref "U12") (pin "1") (pinfunction "VBAT_1") (pintype "power_in"))
      (node (ref "U12") (pin "19") (pinfunction "VDD_19") (pintype "power_in"))
      (node (ref "U12") (pin "32") (pinfunction "VDD_32") (pintype "power_in"))
      (node (ref "U12") (pin "48") (pinfunction "VDD_48") (pintype "power_in"))
      (node (ref "U12") (pin "64") (pinfunction "VDD_64") (pintype "power_in"))
      (node (ref "U2") (pin "19") (pinfunction "VDD3P3_RTC_19") (pintype "power_in"))
      (node (ref "U2") (pin "3") (pinfunction "VDD3P3_3") (pintype "power_in"))
      (node (ref "U2") (pin "37") (pinfunction "VDD3P3_CPU_37") (pintype "power_in"))
      (node (ref "U2") (pin "4") (pinfunction "VDD3P3_4") (pintype "power_in"))
      (node (ref "U4") (pin "1") (pinfunction "+_1") (pintype "passive"))
    )
    (net (code "91") (name "3V3A") (class "Default")
      (node (ref "C1") (pin "2") (pinfunction "2_2") (pintype "passive"))
      (node (ref "C2") (pin "2") (pinfunction "2_2") (pintype "passive"))
      (node (ref "R2") (pin "2") (pinfunction "2_2") (pintype "passive"))
      (node (ref "U2") (pin "1") (pinfunction "VDDA_1") (pintype "power_in"))
      (node (ref "U2") (pin "43") (pinfunction "VDDA_43") (pintype "power_in"))
      (node (ref "U2") (pin "46") (pinfunction "VDDA_46") (pintype "power_in"))
    )
    (net (code "92") (name "AGND") (class "Default")
      (node (ref "C32") (pin "1") (pinfunction "1_1") (pintype "passive"))
      (node (ref "C33") (pin "1") (pinfunction "1_1") (pintype "passive"))
      (node (ref "R26") (pin "1") (pinfunction "1_1") (pintype "passive"))
      (node (ref "U12") (pin "12") (pinfunction "VSSA_12") (pintype "power_in"))
    )
    (net (code "93") (name "AVCC") (class "Default")
      (node (ref "C32") (pin "2") (pinfunction "2_2") (pintype "passive"))
      (node (ref "C33") (pin "2") (pinfunction "2_2") (pintype "passive"))
      (node (ref "R25") (pin "1") (pinfunction "1_1") (pintype "passive"))
      (node (ref "U12") (pin "13") (pinfunction "VDDA_13") (pintype "power_in"))
    )
    (net (code "94") (name "GND") (class "Default")
      (node (ref "1") (pin "12") (pinfunction "VSS_12") (pintype "passive"))
      (node (ref "1") (pin "7") (pinfunction "CS_7") (pintype "passive"))
      (node (ref "1") (pin "9") (pinfunction "DC_9") (pintype "passive"))
      (node (ref "C1") (pin "1") (pinfunction "1_1") (pintype "passive"))
      (node (ref "C10") (pin "1") (pinfunction "1_1") (pintype "passive"))
      (node (ref "C14") (pin "1") (pinfunction "1_1") (pintype "passive"))
      (node (ref "C15") (pin "1") (pinfunction "1_1") (pintype "passive"))
      (node (ref "C16") (pin "1") (pinfunction "1_1") (pintype "passive"))
      (node (ref "C17") (pin "1") (pinfunction "1_1") (pintype "passive"))
      (node (ref "C18") (pin "1") (pinfunction "1_1") (pintype "passive"))
      (node (ref "C19") (pin "1") (pinfunction "1_1") (pintype "passive"))
      (node (ref "C2") (pin "1") (pinfunction "1_1") (pintype "passive"))
      (node (ref "C20") (pin "2") (pinfunction "2_2") (pintype "passive"))
      (node (ref "C21") (pin "1") (pinfunction "1_1") (pintype "passive"))
      (node (ref "C22") (pin "1") (pinfunction "1_1") (pintype "passive"))
      (node (ref "C23") (pin "2") (pinfunction "2_2") (pintype "passive"))
      (node (ref "C24") (pin "1") (pinfunction "1_1") (pintype "passive"))
      (node (ref "C25") (pin "1") (pinfunction "1_1") (pintype "passive"))
      (node (ref "C26") (pin "1") (pinfunction "1_1") (pintype "passive"))
      (node (ref "C27") (pin "1") (pinfunction "1_1") (pintype "passive"))
      (node (ref "C28") (pin "1") (pinfunction "1_1") (pintype "passive"))
      (node (ref "C29") (pin "1") (pinfunction "1_1") (pintype "passive"))
      (node (ref "C3") (pin "2") (pinfunction "2_2") (pintype "passive"))
      (node (ref "C30") (pin "1") (pinfunction "1_1") (pintype "passive"))
      (node (ref "C31") (pin "1") (pinfunction "1_1") (pintype "passive"))
      (node (ref "C34") (pin "1") (pinfunction "1_1") (pintype "passive"))
      (node (ref "C35") (pin "1") (pinfunction "1_1") (pintype "passive"))
      (node (ref "C36") (pin "1") (pinfunction "1_1") (pintype "passive"))
      (node (ref "C37") (pin "1") (pinfunction "1_1") (pintype "passive"))
      (node (ref "C4") (pin "1") (pinfunction "1_1") (pintype "passive"))
      (node (ref "C5") (pin "1") (pinfunction "1_1") (pintype "passive"))
      (node (ref "C6") (pin "2") (pinfunction "2_2") (pintype "passive"))
      (node (ref "C7") (pin "2") (pinfunction "2_2") (pintype "passive"))
      (node (ref "C9") (pin "2") (pinfunction "2_2") (pintype "passive"))
      (node (ref "D3") (pin "1") (pinfunction "1_1") (pintype "passive"))
      (node (ref "D4") (pin "1") (pinfunction "A_1") (pintype "passive"))
      (node (ref "J1") (pin "A1") (pinfunction "GND_A1") (pintype "bidirectional"))
      (node (ref "J1") (pin "B1") (pinfunction "GND2_B1") (pintype "bidirectional"))
      (node (ref "J1") (pin "S1") (pinfunction "SHIELD_S1") (pintype "bidirectional"))
      (node (ref "J1") (pin "S2") (pinfunction "SHIELD_S2") (pintype "bidirectional"))
      (node (ref "J1") (pin "S3") (pinfunction "SHIELD1_S3") (pintype "bidirectional"))
      (node (ref "J1") (pin "S4") (pinfunction "SHIELD1_S4") (pintype "bidirectional"))
      (node (ref "P1") (pin "5") (pinfunction "5_5") (pintype "passive"))
      (node (ref "P1") (pin "6") (pinfunction "6_6") (pintype "passive"))
      (node (ref "P2") (pin "1") (pinfunction "1_1") (pintype "passive"))
      (node (ref "P2") (pin "4") (pinfunction "4_4") (pintype "passive"))
      (node (ref "P3") (pin "3") (pinfunction "3_3") (pintype "passive"))
      (node (ref "Q2") (pin "2") (pinfunction "S_2") (pintype "passive"))
      (node (ref "R10") (pin "1") (pinfunction "1_1") (pintype "passive"))
      (node (ref "R14") (pin "1") (pinfunction "1_1") (pintype "passive"))
      (node (ref "R15") (pin "2") (pinfunction "2_2") (pintype "passive"))
      (node (ref "R18") (pin "1") (pinfunction "1_1") (pintype "passive"))
      (node (ref "R22") (pin "2") (pinfunction "2_2") (pintype "passive"))
      (node (ref "R26") (pin "2") (pinfunction "2_2") (pintype "passive"))
      (node (ref "R35") (pin "1") (pinfunction "1_1") (pintype "passive"))
      (node (ref "R8") (pin "2") (pinfunction "2_2") (pintype "passive"))
      (node (ref "R9") (pin "2") (pinfunction "2_2") (pintype "passive"))
      (node (ref "U1") (pin "29") (pinfunction "HEAT_TAB_29") (pintype "passive"))
      (node (ref "U1") (pin "3") (pinfunction "GND_3") (pintype "passive"))
      (node (ref "U10") (pin "1") (pinfunction "CLKIN_1") (pintype "passive"))
      (node (ref "U10") (pin "11") (pinfunction "FSYNC_11") (pintype "passive"))
      (node (ref "U10") (pin "18") (pinfunction "GND_18") (pintype "passive"))
      (node (ref "U10") (pin "9") (pinfunction "AD0_9") (pintype "passive"))
      (node (ref "U11") (pin "2") (pinfunction "GND_2") (pintype "passive"))
      (node (ref "U12") (pin "18") (pinfunction "VSS_18") (pintype "power_in"))
      (node (ref "U12") (pin "28") (pinfunction "PB2-BOOT1(PB2)_28") (pintype "bidirectional"))
      (node (ref "U12") (pin "60") (pinfunction "BOOT0_60") (pintype "input"))
      (node (ref "U12") (pin "63") (pinfunction "VSS_63") (pintype "power_in"))
      (node (ref "U2") (pin "49") (pinfunction "GND_49") (pintype "power_in"))
      (node (ref "U3") (pin "2") (pinfunction "GND_2") (pintype "passive"))
      (node (ref "U7") (pin "2") (pinfunction "GND_2") (pintype "passive"))
      (node (ref "U8") (pin "2") (pinfunction "GND_2") (pintype "passive"))
      (node (ref "VT1") (pin "2") (pinfunction "E_2") (pintype "passive"))
    )
    (net (code "95") (name "Net-(1-IM1)") (class "Default")
      (node (ref "1") (pin "5") (pinfunction "IM1_5") (pintype "passive"))
      (node (ref "R23") (pin "1") (pinfunction "1_1") (pintype "passive"))
    )
    (net (code "96") (name "Net-(1-IREF)") (class "Default")
      (node (ref "1") (pin "6") (pinfunction "IREF_6") (pintype "passive"))
      (node (ref "R22") (pin "1") (pinfunction "1_1") (pintype "passive"))
    )
    (net (code "97") (name "Net-(1-RES)") (class "Default")
      (node (ref "1") (pin "8") (pinfunction "RES_8") (pintype "passive"))
      (node (ref "C26") (pin "2") (pinfunction "2_2") (pintype "passive"))
      (node (ref "R21") (pin "1") (pinfunction "1_1") (pintype "passive"))
    )
    (net (code "98") (name "Net-(1-VCCOMH)") (class "Default")
      (node (ref "1") (pin "3") (pinfunction "VCCOMH_3") (pintype "passive"))
      (node (ref "C27") (pin "2") (pinfunction "2_2") (pintype "passive"))
    )
    (net (code "99") (name "Net-(D4-K)") (class "Default")
      (node (ref "C12") (pin "1") (pinfunction "1_1") (pintype "passive"))
      (node (ref "C8") (pin "1") (pinfunction "1_1") (pintype "passive"))
      (node (ref "D4") (pin "2") (pinfunction "K_2") (pintype "passive"))
      (node (ref "L1") (pin "1") (pintype "passive"))
      (node (ref "U8") (pin "6") (pinfunction "SW_6") (pintype "passive"))
    )
    (net (code "100") (name "Net-(D5-K)") (class "Default")
      (node (ref "C16") (pin "2") (pinfunction "2_2") (pintype "passive"))
      (node (ref "D5") (pin "2") (pinfunction "K_2") (pintype "passive"))
      (node (ref "R16") (pin "1") (pinfunction "1_1") (pintype "passive"))
      (node (ref "U8") (pin "5") (pinfunction "IN_5") (pintype "passive"))
    )
    (net (code "101") (name "Net-(J1-CC1)") (class "Default")
      (node (ref "J1") (pin "A5") (pinfunction "CC1_A5") (pintype "bidirectional"))
      (node (ref "R9") (pin "1") (pinfunction "1_1") (pintype "passive"))
    )
    (net (code "102") (name "Net-(J1-VCONN)") (class "Default")
      (node (ref "J1") (pin "B5") (pinfunction "VCONN_B5") (pintype "bidirectional"))
      (node (ref "R8") (pin "1") (pinfunction "1_1") (pintype "passive"))
    )
    (net (code "103") (name "Net-(LED1-CATHODE)") (class "Default")
      (node (ref "LED1") (pin "C") (pinfunction "CATHODE_C") (pintype "passive"))
      (node (ref "R18") (pin "2") (pinfunction "2_2") (pintype "passive"))
    )
    (net (code "104") (name "Net-(P3-Pad1)") (class "Default")
      (node (ref "P3") (pin "1") (pinfunction "1_1") (pintype "passive"))
      (node (ref "R27") (pin "1") (pinfunction "1_1") (pintype "passive"))
      (node (ref "R29") (pin "1") (pinfunction "1_1") (pintype "passive"))
    )
    (net (code "105") (name "Net-(Q1A-B1)") (class "Default")
      (node (ref "Q1") (pin "2") (pinfunction "B1_2") (pintype "passive"))
      (node (ref "R4") (pin "2") (pinfunction "2_2") (pintype "passive"))
    )
    (net (code "106") (name "Net-(Q1B-B2)") (class "Default")
      (node (ref "Q1") (pin "5") (pinfunction "B2_5") (pintype "passive"))
      (node (ref "R6") (pin "2") (pinfunction "2_2") (pintype "passive"))
    )
    (net (code "107") (name "Net-(Q2-D)") (class "Default")
      (node (ref "Q2") (pin "3") (pinfunction "D_3") (pintype "passive"))
      (node (ref "U4") (pin "2") (pinfunction "-_2") (pintype "passive"))
    )
    (net (code "108") (name "Net-(Q3-G)") (class "Default")
      (node (ref "Q3") (pin "1") (pinfunction "G_1") (pintype "passive"))
      (node (ref "R12") (pin "1") (pinfunction "1_1") (pintype "passive"))
      (node (ref "VT1") (pin "3") (pinfunction "C_3") (pintype "passive"))
    )
    (net (code "109") (name "Net-(U1-*RST)") (class "Default")
      (node (ref "R1") (pin "2") (pinfunction "2_2") (pintype "passive"))
      (node (ref "U1") (pin "9") (pinfunction "*RST_9") (pintype "passive"))
    )
    (net (code "110") (name "Net-(U1-TXD)") (class "Default")
      (node (ref "R3") (pin "2") (pinfunction "2_2") (pintype "passive"))
      (node (ref "U1") (pin "26") (pinfunction "TXD_26") (pintype "passive"))
    )
    (net (code "111") (name "Net-(U2-LNA_IN)") (class "Default")
      (node (ref "A1") (pin "1") (pinfunction "1_1") (pintype "passive"))
      (node (ref "U2") (pin "2") (pinfunction "LNA_IN_2") (pintype "passive"))
    )
    (net (code "112") (name "Net-(U3-FB)") (class "Default")
      (node (ref "C13") (pin "1") (pinfunction "1_1") (pintype "passive"))
      (node (ref "R33") (pin "1") (pinfunction "1_1") (pintype "passive"))
      (node (ref "R35") (pin "2") (pinfunction "2_2") (pintype "passive"))
      (node (ref "U3") (pin "5") (pinfunction "FB_5") (pintype "passive"))
    )
    (net (code "113") (name "Net-(U3-LX)") (class "Default")
      (node (ref "L2") (pin "1") (pintype "passive"))
      (node (ref "U3") (pin "3") (pinfunction "LX_3") (pintype "passive"))
    )
    (net (code "114") (name "Net-(U3-ON{slash}OFF)") (class "Default")
      (node (ref "R34") (pin "1") (pinfunction "1_1") (pintype "passive"))
      (node (ref "U3") (pin "1") (pinfunction "ON/OFF_1") (pintype "passive"))
    )
    (net (code "115") (name "Net-(U8-BS)") (class "Default")
      (node (ref "C12") (pin "2") (pinfunction "2_2") (pintype "passive"))
      (node (ref "C8") (pin "2") (pinfunction "2_2") (pintype "passive"))
      (node (ref "U8") (pin "1") (pinfunction "BS_1") (pintype "passive"))
    )
    (net (code "116") (name "Net-(U8-EN)") (class "Default")
      (node (ref "R16") (pin "2") (pinfunction "2_2") (pintype "passive"))
      (node (ref "U8") (pin "4") (pinfunction "EN_4") (pintype "passive"))
    )
    (net (code "117") (name "Net-(U8-FB)") (class "Default")
      (node (ref "C11") (pin "2") (pinfunction "2_2") (pintype "passive"))
      (node (ref "R11") (pin "1") (pinfunction "1_1") (pintype "passive"))
      (node (ref "R14") (pin "2") (pinfunction "2_2") (pintype "passive"))
      (node (ref "U8") (pin "3") (pinfunction "FB_3") (pintype "passive"))
    )
    (net (code "118") (name "Net-(U10-CPOUT)") (class "Default")
      (node (ref "C24") (pin "2") (pinfunction "2_2") (pintype "passive"))
      (node (ref "U10") (pin "20") (pinfunction "CPOUT_20") (pintype "passive"))
    )
    (net (code "119") (name "Net-(U10-REGOUT)") (class "Default")
      (node (ref "C23") (pin "1") (pinfunction "1_1") (pintype "passive"))
      (node (ref "U10") (pin "10") (pinfunction "REGOUT_10") (pintype "passive"))
    )
    (net (code "120") (name "Net-(U12A-PH0-OSC_IN(PH0))") (class "Default")
      (node (ref "C7") (pin "1") (pinfunction "1_1") (pintype "passive"))
      (node (ref "R30") (pin "1") (pinfunction "1_1") (pintype "passive"))
      (node (ref "U12") (pin "5") (pinfunction "PH0-OSC_IN(PH0)_5") (pintype "bidirectional"))
      (node (ref "Y1") (pin "3") (pinfunction "OSC2_3") (pintype "passive"))
    )
    (net (code "121") (name "Net-(U12A-PH1-OSC_OUT(PH1))") (class "Default")
      (node (ref "C9") (pin "1") (pinfunction "1_1") (pintype "passive"))
      (node (ref "R30") (pin "2") (pinfunction "2_2") (pintype "passive"))
      (node (ref "U12") (pin "6") (pinfunction "PH1-OSC_OUT(PH1)_6") (pintype "bidirectional"))
      (node (ref "Y1") (pin "1") (pinfunction "OSC1_1") (pintype "passive"))
    )
    (net (code "122") (name "Net-(U12A-VCAP_1)") (class "Default")
      (node (ref "C35") (pin "2") (pinfunction "2_2") (pintype "passive"))
      (node (ref "U12") (pin "31") (pinfunction "VCAP_1_31") (pintype "power_in"))
    )
    (net (code "123") (name "Net-(U12A-VCAP_2)") (class "Default")
      (node (ref "C34") (pin "2") (pinfunction "2_2") (pintype "passive"))
      (node (ref "U12") (pin "47") (pinfunction "VCAP_2_47") (pintype "power_in"))
    )
    (net (code "124") (name "Net-(VT1-B)") (class "Default")
      (node (ref "R13") (pin "2") (pinfunction "2_2") (pintype "passive"))
      (node (ref "R15") (pin "1") (pinfunction "1_1") (pintype "passive"))
      (node (ref "VT1") (pin "1") (pinfunction "B_1") (pintype "passive"))
    )
    (net (code "125") (name "VCC") (class "Default")
      (node (ref "C6") (pin "1") (pinfunction "1_1") (pintype "passive"))
      (node (ref "D2") (pin "2") (pinfunction "K_2") (pintype "passive"))
      (node (ref "D3") (pin "2") (pinfunction "2_2") (pintype "passive"))
      (node (ref "D5") (pin "1") (pinfunction "A_1") (pintype "passive"))
      (node (ref "Q3") (pin "2") (pinfunction "S_2") (pintype "passive"))
      (node (ref "R12") (pin "2") (pinfunction "2_2") (pintype "passive"))
    )
    (net (code "126") (name "VCC_3V3_RD") (class "Default")
      (node (ref "R31") (pin "2") (pinfunction "2_2") (pintype "passive"))
      (node (ref "U7") (pin "1") (pinfunction "VCC_1") (pintype "passive"))
    )
    (net (code "127") (name "VCC_5V") (class "Default")
      (node (ref "1") (pin "2") (pinfunction "VPP_2") (pintype "passive"))
      (node (ref "C11") (pin "1") (pinfunction "1_1") (pintype "passive"))
      (node (ref "C14") (pin "2") (pinfunction "2_2") (pintype "passive"))
      (node (ref "C15") (pin "2") (pinfunction "2_2") (pintype "passive"))
      (node (ref "C17") (pin "2") (pinfunction "2_2") (pintype "passive"))
      (node (ref "L1") (pin "2") (pinfunction "2_2") (pintype "passive"))
      (node (ref "R11") (pin "2") (pinfunction "2_2") (pintype "passive"))
      (node (ref "R29") (pin "2") (pinfunction "2_2") (pintype "passive"))
      (node (ref "R34") (pin "2") (pinfunction "2_2") (pintype "passive"))
      (node (ref "U3") (pin "4") (pinfunction "VIN_4") (pintype "passive"))
    )
    (net (code "128") (name "VCC_IN") (class "Default")
      (node (ref "D2") (pin "1") (pinfunction "A_1") (pintype "passive"))
      (node (ref "P1") (pin "1") (pinfunction "1_1") (pintype "passive"))
      (node (ref "P1") (pin "2") (pinfunction "2_2") (pintype "passive"))
    )
    (net (code "129") (name "VDD_USB") (class "Default")
      (node (ref "J1") (pin "A4") (pinfunction "VBUS_A4") (pintype "bidirectional"))
      (node (ref "J1") (pin "A9") (pinfunction "VBUS1_A9") (pintype "bidirectional"))
      (node (ref "J1") (pin "B4") (pinfunction "VBUS2_B4") (pintype "bidirectional"))
      (node (ref "J1") (pin "B9") (pinfunction "VBUS3_B9") (pintype "bidirectional"))
      (node (ref "R1") (pin "1") (pinfunction "1_1") (pintype "passive"))
      (node (ref "U1") (pin "7") (pinfunction "REGIN_7") (pintype "passive"))
      (node (ref "U1") (pin "8") (pinfunction "VBUS_8") (pintype "passive"))
    )
    (net (code "130") (name "unconnected-(1-NC1-Pad1)") (class "Default")
      (node (ref "1") (pin "1") (pinfunction "NC1_1") (pintype "passive"))
    )
    (net (code "131") (name "unconnected-(1-NC2-Pad13)") (class "Default")
      (node (ref "1") (pin "13") (pinfunction "NC2_13") (pintype "passive"))
    )
    (net (code "132") (name "unconnected-(J1-GND1-PadA12)") (class "Default")
      (node (ref "J1") (pin "A12") (pinfunction "GND1_A12") (pintype "bidirectional"))
    )
    (net (code "133") (name "unconnected-(J1-GND3-PadB12)") (class "Default")
      (node (ref "J1") (pin "B12") (pinfunction "GND3_B12") (pintype "bidirectional"))
    )
    (net (code "134") (name "unconnected-(J1-SBU1-PadA8)") (class "Default")
      (node (ref "J1") (pin "A8") (pinfunction "SBU1_A8") (pintype "bidirectional"))
    )
    (net (code "135") (name "unconnected-(J1-SBU2-PadB8)") (class "Default")
      (node (ref "J1") (pin "B8") (pinfunction "SBU2_B8") (pintype "bidirectional"))
    )
    (net (code "136") (name "unconnected-(J1-SSRXN1-PadB10)") (class "Default")
      (node (ref "J1") (pin "B10") (pinfunction "SSRXN1_B10") (pintype "bidirectional"))
    )
    (net (code "137") (name "unconnected-(J1-SSRXN2-PadA10)") (class "Default")
      (node (ref "J1") (pin "A10") (pinfunction "SSRXN2_A10") (pintype "bidirectional"))
    )
    (net (code "138") (name "unconnected-(J1-SSRXP1-PadB11)") (class "Default")
      (node (ref "J1") (pin "B11") (pinfunction "SSRXP1_B11") (pintype "bidirectional"))
    )
    (net (code "139") (name "unconnected-(J1-SSRXP2-PadA11)") (class "Default")
      (node (ref "J1") (pin "A11") (pinfunction "SSRXP2_A11") (pintype "bidirectional"))
    )
    (net (code "140") (name "unconnected-(J1-SSTXN1-PadA3)") (class "Default")
      (node (ref "J1") (pin "A3") (pinfunction "SSTXN1_A3") (pintype "bidirectional"))
    )
    (net (code "141") (name "unconnected-(J1-SSTXN2-PadB3)") (class "Default")
      (node (ref "J1") (pin "B3") (pinfunction "SSTXN2_B3") (pintype "bidirectional"))
    )
    (net (code "142") (name "unconnected-(J1-SSTXP1-PadA2)") (class "Default")
      (node (ref "J1") (pin "A2") (pinfunction "SSTXP1_A2") (pintype "bidirectional"))
    )
    (net (code "143") (name "unconnected-(J1-SSTXP2-PadB2)") (class "Default")
      (node (ref "J1") (pin "B2") (pinfunction "SSTXP2_B2") (pintype "bidirectional"))
    )
    (net (code "144") (name "unconnected-(U1-*SUSPEND-Pad11)") (class "Default")
      (node (ref "U1") (pin "11") (pinfunction "*SUSPEND_11") (pintype "passive"))
    )
    (net (code "145") (name "unconnected-(U1-CTS-Pad23)") (class "Default")
      (node (ref "U1") (pin "23") (pinfunction "CTS_23") (pintype "passive"))
    )
    (net (code "146") (name "unconnected-(U1-DCD-Pad1)") (class "Default")
      (node (ref "U1") (pin "1") (pinfunction "DCD_1") (pintype "passive"))
    )
    (net (code "147") (name "unconnected-(U1-DSR-Pad27)") (class "Default")
      (node (ref "U1") (pin "27") (pinfunction "DSR_27") (pintype "passive"))
    )
    (net (code "148") (name "unconnected-(U1-NC-Pad10)") (class "Default")
      (node (ref "U1") (pin "10") (pinfunction "NC_10") (pintype "passive"))
    )
    (net (code "149") (name "unconnected-(U1-NC-Pad13)") (class "Default")
      (node (ref "U1") (pin "13") (pinfunction "NC_13") (pintype "passive"))
    )
    (net (code "150") (name "unconnected-(U1-NC-Pad14)") (class "Default")
      (node (ref "U1") (pin "14") (pinfunction "NC_14") (pintype "passive"))
    )
    (net (code "151") (name "unconnected-(U1-NC-Pad15)") (class "Default")
      (node (ref "U1") (pin "15") (pinfunction "NC_15") (pintype "passive"))
    )
    (net (code "152") (name "unconnected-(U1-NC-Pad16)") (class "Default")
      (node (ref "U1") (pin "16") (pinfunction "NC_16") (pintype "passive"))
    )
    (net (code "153") (name "unconnected-(U1-NC-Pad17)") (class "Default")
      (node (ref "U1") (pin "17") (pinfunction "NC_17") (pintype "passive"))
    )
    (net (code "154") (name "unconnected-(U1-NC-Pad18)") (class "Default")
      (node (ref "U1") (pin "18") (pinfunction "NC_18") (pintype "passive"))
    )
    (net (code "155") (name "unconnected-(U1-NC-Pad19)") (class "Default")
      (node (ref "U1") (pin "19") (pinfunction "NC_19") (pintype "passive"))
    )
    (net (code "156") (name "unconnected-(U1-NC-Pad20)") (class "Default")
      (node (ref "U1") (pin "20") (pinfunction "NC_20") (pintype "passive"))
    )
    (net (code "157") (name "unconnected-(U1-NC-Pad21)") (class "Default")
      (node (ref "U1") (pin "21") (pinfunction "NC_21") (pintype "passive"))
    )
    (net (code "158") (name "unconnected-(U1-NC-Pad22)") (class "Default")
      (node (ref "U1") (pin "22") (pinfunction "NC_22") (pintype "passive"))
    )
    (net (code "159") (name "unconnected-(U1-RI-Pad2)") (class "Default")
      (node (ref "U1") (pin "2") (pinfunction "RI_2") (pintype "passive"))
    )
    (net (code "160") (name "unconnected-(U1-SUSPEND-Pad12)") (class "Default")
      (node (ref "U1") (pin "12") (pinfunction "SUSPEND_12") (pintype "passive"))
    )
    (net (code "161") (name "unconnected-(U1-VDD-Pad6)") (class "Default")
      (node (ref "U1") (pin "6") (pinfunction "VDD_6") (pintype "passive"))
    )
    (net (code "162") (name "unconnected-(U2-CAP1_NC-Pad48)") (class "Default")
      (node (ref "U2") (pin "48") (pinfunction "CAP1_NC_48") (pintype "passive"))
    )
    (net (code "163") (name "unconnected-(U2-CAP2_NC-Pad47)") (class "Default")
      (node (ref "U2") (pin "47") (pinfunction "CAP2_NC_47") (pintype "passive"))
    )
    (net (code "164") (name "unconnected-(U2-VDD_SDIO_NC-Pad26)") (class "Default")
      (node (ref "U2") (pin "26") (pinfunction "VDD_SDIO_NC_26") (pintype "passive"))
    )
    (net (code "165") (name "unconnected-(U2-XTAL_N_NC-Pad44)") (class "Default")
      (node (ref "U2") (pin "44") (pinfunction "XTAL_N_NC_44") (pintype "passive"))
    )
    (net (code "166") (name "unconnected-(U2-XTAL_P_NC-Pad45)") (class "Default")
      (node (ref "U2") (pin "45") (pinfunction "XTAL_P_NC_45") (pintype "passive"))
    )
    (net (code "167") (name "unconnected-(U10-A_CL-Pad7)") (class "Default")
      (node (ref "U10") (pin "7") (pinfunction "A_CL_7") (pintype "passive"))
    )
    (net (code "168") (name "unconnected-(U10-A_DA-Pad6)") (class "Default")
      (node (ref "U10") (pin "6") (pinfunction "A_DA_6") (pintype "passive"))
    )
    (net (code "169") (name "unconnected-(U10-CLKOUT-Pad22)") (class "Default")
      (node (ref "U10") (pin "22") (pinfunction "CLKOUT_22") (pintype "passive"))
    )
    (net (code "170") (name "unconnected-(U10-INT-Pad12)") (class "Default")
      (node (ref "U10") (pin "12") (pinfunction "INT_12") (pintype "passive"))
    )
    (net (code "171") (name "unconnected-(U10-NC-Pad2)") (class "Default")
      (node (ref "U10") (pin "2") (pinfunction "NC_2") (pintype "passive"))
    )
    (net (code "172") (name "unconnected-(U10-NC-Pad3)") (class "Default")
      (node (ref "U10") (pin "3") (pinfunction "NC_3") (pintype "passive"))
    )
    (net (code "173") (name "unconnected-(U10-NC-Pad4)") (class "Default")
      (node (ref "U10") (pin "4") (pinfunction "NC_4") (pintype "passive"))
    )
    (net (code "174") (name "unconnected-(U10-NC-Pad5)") (class "Default")
      (node (ref "U10") (pin "5") (pinfunction "NC_5") (pintype "passive"))
    )
    (net (code "175") (name "unconnected-(U10-NC-Pad14)") (class "Default")
      (node (ref "U10") (pin "14") (pinfunction "NC_14") (pintype "passive"))
    )
    (net (code "176") (name "unconnected-(U10-NC-Pad15)") (class "Default")
      (node (ref "U10") (pin "15") (pinfunction "NC_15") (pintype "passive"))
    )
    (net (code "177") (name "unconnected-(U10-NC-Pad16)") (class "Default")
      (node (ref "U10") (pin "16") (pinfunction "NC_16") (pintype "passive"))
    )
    (net (code "178") (name "unconnected-(U10-NC-Pad17)") (class "Default")
      (node (ref "U10") (pin "17") (pinfunction "NC_17") (pintype "passive"))
    )
    (net (code "179") (name "unconnected-(U10-RESV-Pad19)") (class "Default")
      (node (ref "U10") (pin "19") (pinfunction "RESV_19") (pintype "passive"))
    )
    (net (code "180") (name "unconnected-(U10-RESV-Pad21)") (class "Default")
      (node (ref "U10") (pin "21") (pinfunction "RESV_21") (pintype "passive"))
    )
    (net (code "181") (name "unconnected-(U11-NC-Pad5)") (class "Default")
      (node (ref "U11") (pin "5") (pinfunction "NC_5") (pintype "passive"))
    )
    (net (code "182") (name "unconnected-(U11-NC-Pad8)") (class "Default")
      (node (ref "U11") (pin "8") (pinfunction "NC_8") (pintype "passive"))
    )
  )
)
